# Sem_2_Lab_Project_-_Simple_Voice_Recorde.net
KiCad netlist of a schematic drawn in Altium Designer
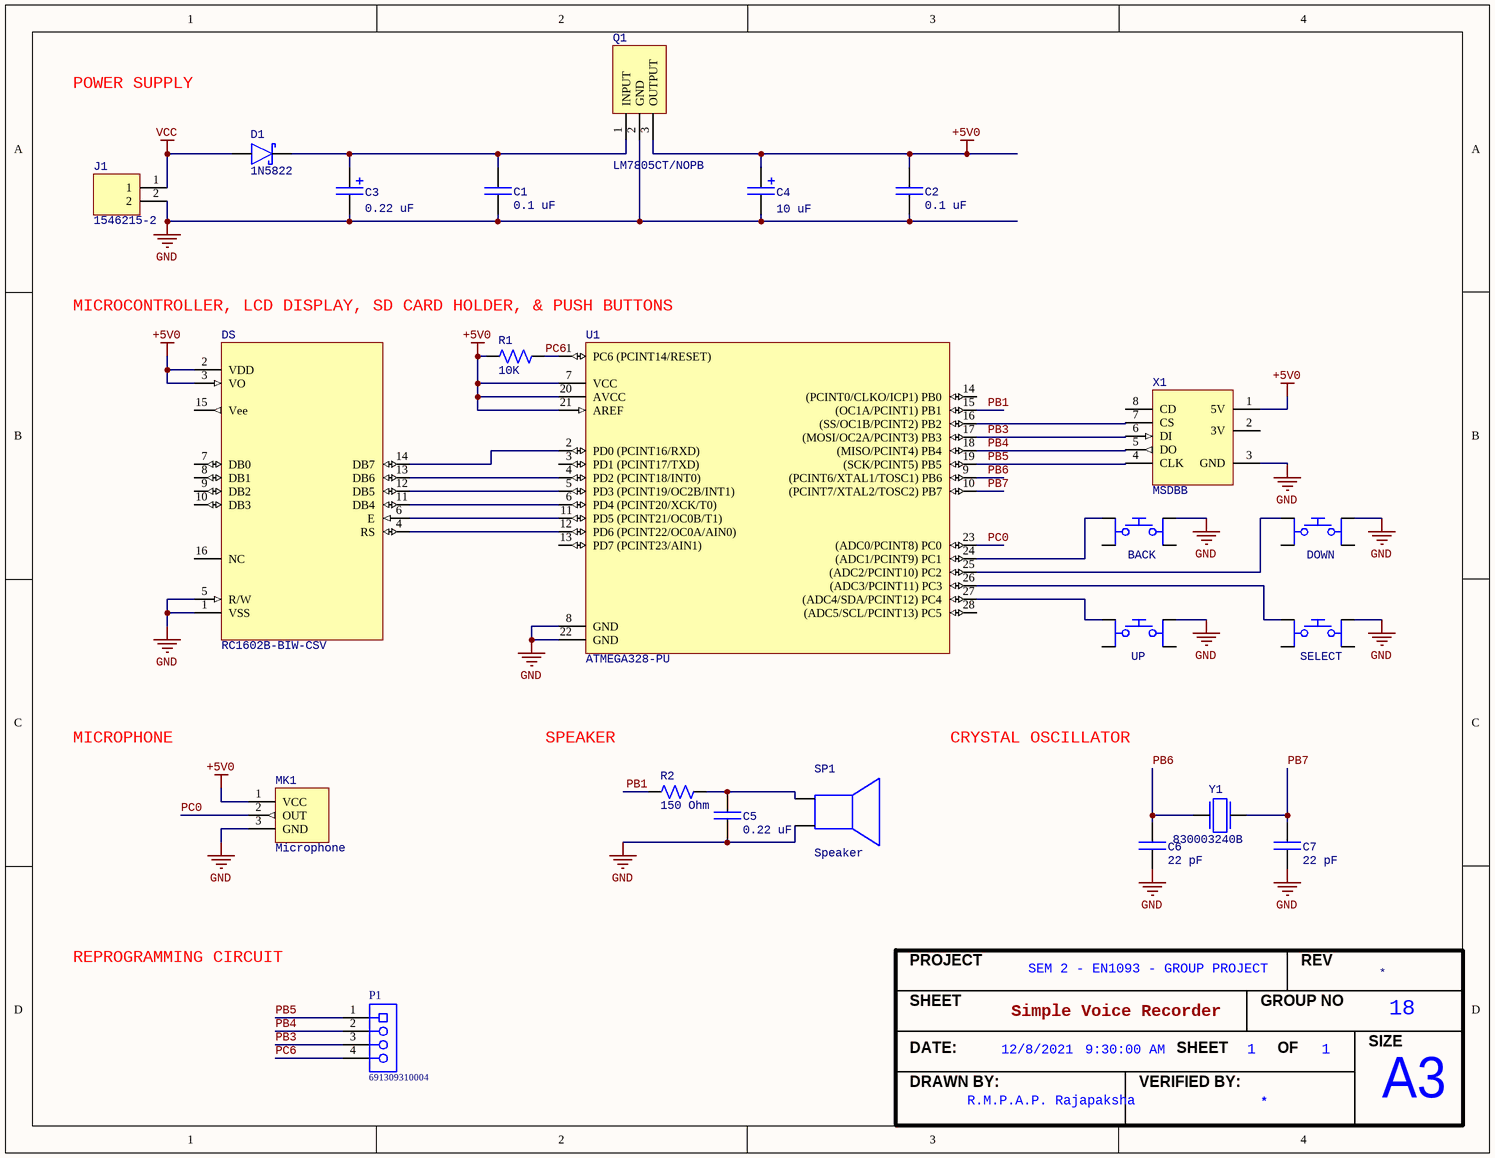
[diagram p0: Sem 2 Lab Project - Simple Voice Recorder.SchDoc]

(export (version "E")
  (design (tool "Eeschema 10.0.6"))
  (components
    (comp (ref "BACK")
      (value "Push Button")
      (footprint "1825910-6")
      (libsource (lib "Simple Voice Recorder") (part "Push Button"))
    )
    (comp (ref "C1")
      (value "0.1 uF")
      (footprint "DE6E3KJ222MN3A")
      (description "Non-polarized Cap")
      (libsource (lib "Simple Voice Recorder") (part "Non-polarized Cap"))
    )
    (comp (ref "C2")
      (value "0.1 uF")
      (footprint "DE6E3KJ222MN3A")
      (description "Non-polarized Cap")
      (libsource (lib "Simple Voice Recorder") (part "Non-polarized Cap"))
    )
    (comp (ref "C3")
      (value "0.22 uF")
      (footprint "CAPPRD500W60D1000H1600-V-000-300")
      (description "Through Hole Capacitor, Polarized Radial Diameter")
      (libsource (lib "Simple Voice Recorder") (part "Polarized Cap"))
    )
    (comp (ref "C4")
      (value "10 uF")
      (footprint "CAPPRD500W60D1000H1600-V-000-300")
      (description "Through Hole Capacitor, Polarized Radial Diameter")
      (libsource (lib "Simple Voice Recorder") (part "Polarized Cap"))
    )
    (comp (ref "C5")
      (value "0.22 uF")
      (footprint "DE6E3KJ222MN3A")
      (description "Non-polarized Cap")
      (libsource (lib "Simple Voice Recorder") (part "Non-polarized Cap"))
    )
    (comp (ref "C6")
      (value "22 pF")
      (footprint "DE6E3KJ222MN3A")
      (description "Non-polarized Cap")
      (libsource (lib "Simple Voice Recorder") (part "Non-polarized Cap"))
    )
    (comp (ref "C7")
      (value "22 pF")
      (footprint "DE6E3KJ222MN3A")
      (description "Non-polarized Cap")
      (libsource (lib "Simple Voice Recorder") (part "Non-polarized Cap"))
    )
    (comp (ref "D1")
      (value "1N5822")
      (footprint "1N5822")
      (description "Diode Schottky 40V 3A Through Hole")
      (libsource (lib "Simple Voice Recorder") (part "Schottky Diode"))
    )
    (comp (ref "DOWN")
      (value "Push Button")
      (footprint "1825910-6")
      (libsource (lib "Simple Voice Recorder") (part "Push Button"))
    )
    (comp (ref "DS")
      (value "RC1602B-BIW-CSV")
      (footprint "RC1602B-BIW-CSV")
      (description "Display: LCD; alphanumeric; STN Negative; 16x2; blue; LED; PIN: 16")
      (libsource (lib "Simple Voice Recorder") (part "RC1602B-BIW-CSV"))
    )
    (comp (ref "J1")
      (value "1546215-2")
      (footprint "1546215-2")
      (description "TERMI-BLOK PCB MOUNT, 90 2P")
      (libsource (lib "Simple Voice Recorder") (part "Connection Terminal"))
    )
    (comp (ref "MK1")
      (value "Microphone")
      (footprint "Adafruit Max4466")
      (libsource (lib "Simple Voice Recorder") (part "Microphone"))
    )
    (comp (ref "P1")
      (value "691309310004")
      (footprint "691309310004")
      (description "Serie 3093 - 3.81mm Horizontal Reversed PCB Header WR-TBL, 4 pin")
      (fields (field (name "MANUFACTURER") "Wurth Elektronik") (field (name "PUBLISHER") "WurthElektronik"))
      (libsource (lib "Altium Content Vault") (part "WE-CN-1P-F-R4"))
    )
    (comp (ref "Q1")
      (value "LM7805CT/NOPB")
      (footprint "LM7805CT/NOPB")
      (description "1.5-A, 30-V, linear voltage regulator 3-TO-220 0 to 125")
      (libsource (lib "Simple Voice Recorder") (part "Voltage Regulator"))
    )
    (comp (ref "R1")
      (value "10K")
      (footprint "RESAD800W55L650D230-100-300_SEI_CF14_CFM12")
      (description "Resistor")
      (libsource (lib "Simple Voice Recorder") (part "Resistor"))
    )
    (comp (ref "R2")
      (value "150 Ohm")
      (footprint "RESAD800W55L650D230-100-300_SEI_CF14_CFM12")
      (description "Resistor")
      (libsource (lib "Simple Voice Recorder") (part "Resistor"))
    )
    (comp (ref "SELECT")
      (value "Push Button")
      (footprint "1825910-6")
      (libsource (lib "Simple Voice Recorder") (part "Push Button"))
    )
    (comp (ref "SP1")
      (value "Speaker")
      (footprint "AST-01708MR-R")
      (fields (field (name "MANUFACTURER") "PUI Audio Inc."))
      (libsource (lib "Simple Voice Recorder") (part "Speaker"))
    )
    (comp (ref "U1")
      (value "ATMEGA328-PU")
      (footprint "ATMEGA328-PU")
      (description "AVR AVRÂ® ATmega Microcontroller IC 8-Bit 20MHz 32KB (16K x 16) FLASH 28-PDIP")
      (fields (field (name "MANUFACTURER") "Microchip Technology Inc."))
      (libsource (lib "Simple Voice Recorder") (part "ATMEGA328-PU"))
    )
    (comp (ref "UP")
      (value "Push Button")
      (footprint "1825910-6")
      (libsource (lib "Simple Voice Recorder") (part "Push Button"))
    )
    (comp (ref "X1")
      (value "MSDBB")
      (footprint "Micro SD Card Breakout Board")
      (description "Micro SD Card Breakout Board")
      (fields (field (name "MANUFACTURER") "Adafruit Industries"))
      (libsource (lib "Simple Voice Recorder") (part "Micro SD Card Breakout Board"))
    )
    (comp (ref "Y1")
      (value "830003240B")
      (footprint "830003240B")
      (description "Crystal Oscillator")
      (libsource (lib "Simple Voice Recorder") (part "830003240B"))
    )
  )
  (nets
    (net (code "1") (name "+5V0") (class "Default")
      (node (ref "C2") (pin "2") (pintype "passive"))
      (node (ref "C4") (pin "1") (pintype "passive"))
      (node (ref "DS") (pin "2") (pinfunction "VDD_2") (pintype "power_in"))
      (node (ref "DS") (pin "3") (pinfunction "VO_3") (pintype "input"))
      (node (ref "MK1") (pin "1") (pinfunction "VCC_1") (pintype "power_in"))
      (node (ref "Q1") (pin "3") (pinfunction "OUTPUT_3") (pintype "power_in"))
      (node (ref "R1") (pin "2") (pintype "passive"))
      (node (ref "U1") (pin "20") (pinfunction "AVCC_20") (pintype "power_in"))
      (node (ref "U1") (pin "21") (pinfunction "AREF_21") (pintype "input"))
      (node (ref "U1") (pin "7") (pinfunction "VCC_7") (pintype "power_in"))
      (node (ref "X1") (pin "1") (pinfunction "5V_1") (pintype "power_in"))
    )
    (net (code "2") (name "/PB1") (class "Default")
      (node (ref "R2") (pin "2") (pintype "passive"))
      (node (ref "U1") (pin "15") (pinfunction "(OC1A/PCINT1)_PB1_15") (pintype "bidirectional"))
    )
    (net (code "3") (name "/PB3") (class "Default")
      (node (ref "P1") (pin "3") (pinfunction "3_3") (pintype "passive"))
      (node (ref "U1") (pin "17") (pinfunction "(MOSI/OC2A/PCINT3)_PB3_17") (pintype "bidirectional"))
      (node (ref "X1") (pin "6") (pinfunction "DI_6") (pintype "input"))
    )
    (net (code "4") (name "/PB4") (class "Default")
      (node (ref "P1") (pin "2") (pinfunction "2_2") (pintype "passive"))
      (node (ref "U1") (pin "18") (pinfunction "(MISO/PCINT4)_PB4_18") (pintype "bidirectional"))
      (node (ref "X1") (pin "5") (pinfunction "DO_5") (pintype "output"))
    )
    (net (code "5") (name "/PB5") (class "Default")
      (node (ref "P1") (pin "1") (pinfunction "1_1") (pintype "passive"))
      (node (ref "U1") (pin "19") (pinfunction "(SCK/PCINT5)_PB5_19") (pintype "bidirectional"))
      (node (ref "X1") (pin "4") (pinfunction "CLK_4") (pintype "passive"))
    )
    (net (code "6") (name "/PB6") (class "Default")
      (node (ref "C6") (pin "2") (pintype "passive"))
      (node (ref "U1") (pin "9") (pinfunction "(PCINT6/XTAL1/TOSC1)_PB6_9") (pintype "bidirectional"))
      (node (ref "Y1") (pin "1") (pintype "passive"))
    )
    (net (code "7") (name "/PB7") (class "Default")
      (node (ref "C7") (pin "2") (pintype "passive"))
      (node (ref "U1") (pin "10") (pinfunction "(PCINT7/XTAL2/TOSC2)_PB7_10") (pintype "bidirectional"))
      (node (ref "Y1") (pin "2") (pinfunction "2_2") (pintype "passive"))
    )
    (net (code "8") (name "/PC0") (class "Default")
      (node (ref "MK1") (pin "2") (pinfunction "OUT_2") (pintype "output"))
      (node (ref "U1") (pin "23") (pinfunction "(ADC0/PCINT8)_PC0_23") (pintype "bidirectional"))
    )
    (net (code "9") (name "/PC6") (class "Default")
      (node (ref "P1") (pin "4") (pinfunction "4_4") (pintype "passive"))
      (node (ref "R1") (pin "1") (pintype "passive"))
      (node (ref "U1") (pin "1") (pinfunction "PC6_(PCINT14/RESET)_1") (pintype "bidirectional"))
    )
    (net (code "10") (name "GND") (class "Default")
      (node (ref "BACK") (pin "2") (pintype "passive"))
      (node (ref "C1") (pin "1") (pintype "passive"))
      (node (ref "C2") (pin "1") (pintype "passive"))
      (node (ref "C3") (pin "2") (pintype "passive"))
      (node (ref "C4") (pin "2") (pintype "passive"))
      (node (ref "C5") (pin "1") (pintype "passive"))
      (node (ref "C6") (pin "1") (pintype "passive"))
      (node (ref "C7") (pin "1") (pintype "passive"))
      (node (ref "DOWN") (pin "2") (pintype "passive"))
      (node (ref "DS") (pin "1") (pinfunction "VSS_1") (pintype "power_in"))
      (node (ref "DS") (pin "5") (pinfunction "R/W_5") (pintype "input"))
      (node (ref "J1") (pin "2") (pinfunction "2_2") (pintype "power_in"))
      (node (ref "MK1") (pin "3") (pinfunction "GND_3") (pintype "power_in"))
      (node (ref "Q1") (pin "2") (pinfunction "GND_2") (pintype "power_in"))
      (node (ref "SELECT") (pin "2") (pintype "passive"))
      (node (ref "SP1") (pin "2") (pintype "passive"))
      (node (ref "U1") (pin "22") (pinfunction "GND_22") (pintype "power_in"))
      (node (ref "U1") (pin "8") (pinfunction "GND_8") (pintype "power_in"))
      (node (ref "UP") (pin "2") (pintype "passive"))
      (node (ref "X1") (pin "3") (pinfunction "GND_3") (pintype "power_in"))
    )
    (net (code "11") (name "Net-(BACK-*)") (class "Default")
      (node (ref "BACK") (pin "1") (pinfunction "*_1") (pintype "passive"))
      (node (ref "U1") (pin "24") (pinfunction "(ADC1/PCINT9)_PC1_24") (pintype "bidirectional"))
    )
    (net (code "12") (name "Net-(C5-Pad2)") (class "Default")
      (node (ref "C5") (pin "2") (pintype "passive"))
      (node (ref "R2") (pin "1") (pintype "passive"))
      (node (ref "SP1") (pin "1") (pintype "passive"))
    )
    (net (code "13") (name "Net-(DOWN-*)") (class "Default")
      (node (ref "DOWN") (pin "1") (pinfunction "*_1") (pintype "passive"))
      (node (ref "U1") (pin "25") (pinfunction "(ADC2/PCINT10)_PC2_25") (pintype "bidirectional"))
    )
    (net (code "14") (name "Net-(DS-DB4)") (class "Default")
      (node (ref "DS") (pin "11") (pinfunction "DB4_11") (pintype "bidirectional"))
      (node (ref "U1") (pin "6") (pinfunction "PD4_(PCINT20/XCK/T0)_6") (pintype "bidirectional"))
    )
    (net (code "15") (name "Net-(DS-DB5)") (class "Default")
      (node (ref "DS") (pin "12") (pinfunction "DB5_12") (pintype "bidirectional"))
      (node (ref "U1") (pin "5") (pinfunction "PD3_(PCINT19/OC2B/INT1)_5") (pintype "bidirectional"))
    )
    (net (code "16") (name "Net-(DS-DB6)") (class "Default")
      (node (ref "DS") (pin "13") (pinfunction "DB6_13") (pintype "bidirectional"))
      (node (ref "U1") (pin "4") (pinfunction "PD2_(PCINT18/INT0)_4") (pintype "bidirectional"))
    )
    (net (code "17") (name "Net-(DS-DB7)") (class "Default")
      (node (ref "DS") (pin "14") (pinfunction "DB7_14") (pintype "bidirectional"))
      (node (ref "U1") (pin "2") (pinfunction "PD0_(PCINT16/RXD)_2") (pintype "bidirectional"))
    )
    (net (code "18") (name "Net-(DS-E)") (class "Default")
      (node (ref "DS") (pin "6") (pinfunction "E_6") (pintype "input"))
      (node (ref "U1") (pin "11") (pinfunction "PD5_(PCINT21/OC0B/T1)_11") (pintype "bidirectional"))
    )
    (net (code "19") (name "Net-(DS-RS)") (class "Default")
      (node (ref "DS") (pin "4") (pinfunction "RS_4") (pintype "bidirectional"))
      (node (ref "U1") (pin "12") (pinfunction "PD6_(PCINT22/OC0A/AIN0)_12") (pintype "bidirectional"))
    )
    (net (code "20") (name "Net-(Q1-INPUT)") (class "Default")
      (node (ref "C1") (pin "2") (pintype "passive"))
      (node (ref "C3") (pin "1") (pintype "passive"))
      (node (ref "D1") (pin "C") (pintype "passive"))
      (node (ref "Q1") (pin "1") (pinfunction "INPUT_1") (pintype "power_in"))
    )
    (net (code "21") (name "Net-(SELECT-*)") (class "Default")
      (node (ref "SELECT") (pin "1") (pinfunction "*_1") (pintype "passive"))
      (node (ref "U1") (pin "26") (pinfunction "(ADC3/PCINT11)_PC3_26") (pintype "bidirectional"))
    )
    (net (code "22") (name "Net-(U1-(ADC4{slash}SDA{slash}PCINT12)_PC4)") (class "Default")
      (node (ref "U1") (pin "27") (pinfunction "(ADC4/SDA/PCINT12)_PC4_27") (pintype "bidirectional"))
      (node (ref "UP") (pin "1") (pinfunction "*_1") (pintype "passive"))
    )
    (net (code "23") (name "Net-(U1-(SS{slash}OC1B{slash}PCINT2)_PB2)") (class "Default")
      (node (ref "U1") (pin "16") (pinfunction "(SS/OC1B/PCINT2)_PB2_16") (pintype "bidirectional"))
      (node (ref "X1") (pin "7") (pinfunction "CS_7") (pintype "passive"))
    )
    (net (code "24") (name "VCC") (class "Default")
      (node (ref "D1") (pin "A") (pintype "passive"))
      (node (ref "J1") (pin "1") (pinfunction "1_1") (pintype "power_in"))
    )
    (net (code "25") (name "unconnected-(BACK-Pad3)") (class "Default")
      (node (ref "BACK") (pin "3") (pintype "passive"))
    )
    (net (code "26") (name "unconnected-(BACK-Pad4)") (class "Default")
      (node (ref "BACK") (pin "4") (pintype "passive"))
    )
    (net (code "27") (name "unconnected-(DOWN-Pad3)") (class "Default")
      (node (ref "DOWN") (pin "3") (pintype "passive"))
    )
    (net (code "28") (name "unconnected-(DOWN-Pad4)") (class "Default")
      (node (ref "DOWN") (pin "4") (pintype "passive"))
    )
    (net (code "29") (name "unconnected-(DS-DB0-Pad7)") (class "Default")
      (node (ref "DS") (pin "7") (pinfunction "DB0_7") (pintype "bidirectional"))
    )
    (net (code "30") (name "unconnected-(DS-DB1-Pad8)") (class "Default")
      (node (ref "DS") (pin "8") (pinfunction "DB1_8") (pintype "bidirectional"))
    )
    (net (code "31") (name "unconnected-(DS-DB2-Pad9)") (class "Default")
      (node (ref "DS") (pin "9") (pinfunction "DB2_9") (pintype "bidirectional"))
    )
    (net (code "32") (name "unconnected-(DS-DB3-Pad10)") (class "Default")
      (node (ref "DS") (pin "10") (pinfunction "DB3_10") (pintype "bidirectional"))
    )
    (net (code "33") (name "unconnected-(DS-NC-Pad16)") (class "Default")
      (node (ref "DS") (pin "16") (pinfunction "NC_16") (pintype "passive"))
    )
    (net (code "34") (name "unconnected-(DS-Vee-Pad15)") (class "Default")
      (node (ref "DS") (pin "15") (pinfunction "Vee_15") (pintype "output"))
    )
    (net (code "35") (name "unconnected-(SELECT-Pad3)") (class "Default")
      (node (ref "SELECT") (pin "3") (pintype "passive"))
    )
    (net (code "36") (name "unconnected-(SELECT-Pad4)") (class "Default")
      (node (ref "SELECT") (pin "4") (pintype "passive"))
    )
    (net (code "37") (name "unconnected-(U1-(ADC5{slash}SCL{slash}PCINT13)_PC5-Pad28)") (class "Default")
      (node (ref "U1") (pin "28") (pinfunction "(ADC5/SCL/PCINT13)_PC5_28") (pintype "bidirectional"))
    )
    (net (code "38") (name "unconnected-(U1-(PCINT0{slash}CLKO{slash}ICP1)_PB0-Pad14)") (class "Default")
      (node (ref "U1") (pin "14") (pinfunction "(PCINT0/CLKO/ICP1)_PB0_14") (pintype "bidirectional"))
    )
    (net (code "39") (name "unconnected-(U1-PD1_(PCINT17{slash}TXD)-Pad3)") (class "Default")
      (node (ref "U1") (pin "3") (pinfunction "PD1_(PCINT17/TXD)_3") (pintype "bidirectional"))
    )
    (net (code "40") (name "unconnected-(U1-PD7_(PCINT23{slash}AIN1)-Pad13)") (class "Default")
      (node (ref "U1") (pin "13") (pinfunction "PD7_(PCINT23/AIN1)_13") (pintype "bidirectional"))
    )
    (net (code "41") (name "unconnected-(UP-Pad3)") (class "Default")
      (node (ref "UP") (pin "3") (pintype "passive"))
    )
    (net (code "42") (name "unconnected-(UP-Pad4)") (class "Default")
      (node (ref "UP") (pin "4") (pintype "passive"))
    )
    (net (code "43") (name "unconnected-(X1-3V-Pad2)") (class "Default")
      (node (ref "X1") (pin "2") (pinfunction "3V_2") (pintype "power_in"))
    )
    (net (code "44") (name "unconnected-(X1-CD-Pad8)") (class "Default")
      (node (ref "X1") (pin "8") (pinfunction "CD_8") (pintype "passive"))
    )
  )
)
